# DC27-bottom-krux.net
KiCad netlist of a schematic drawn in EAGLE
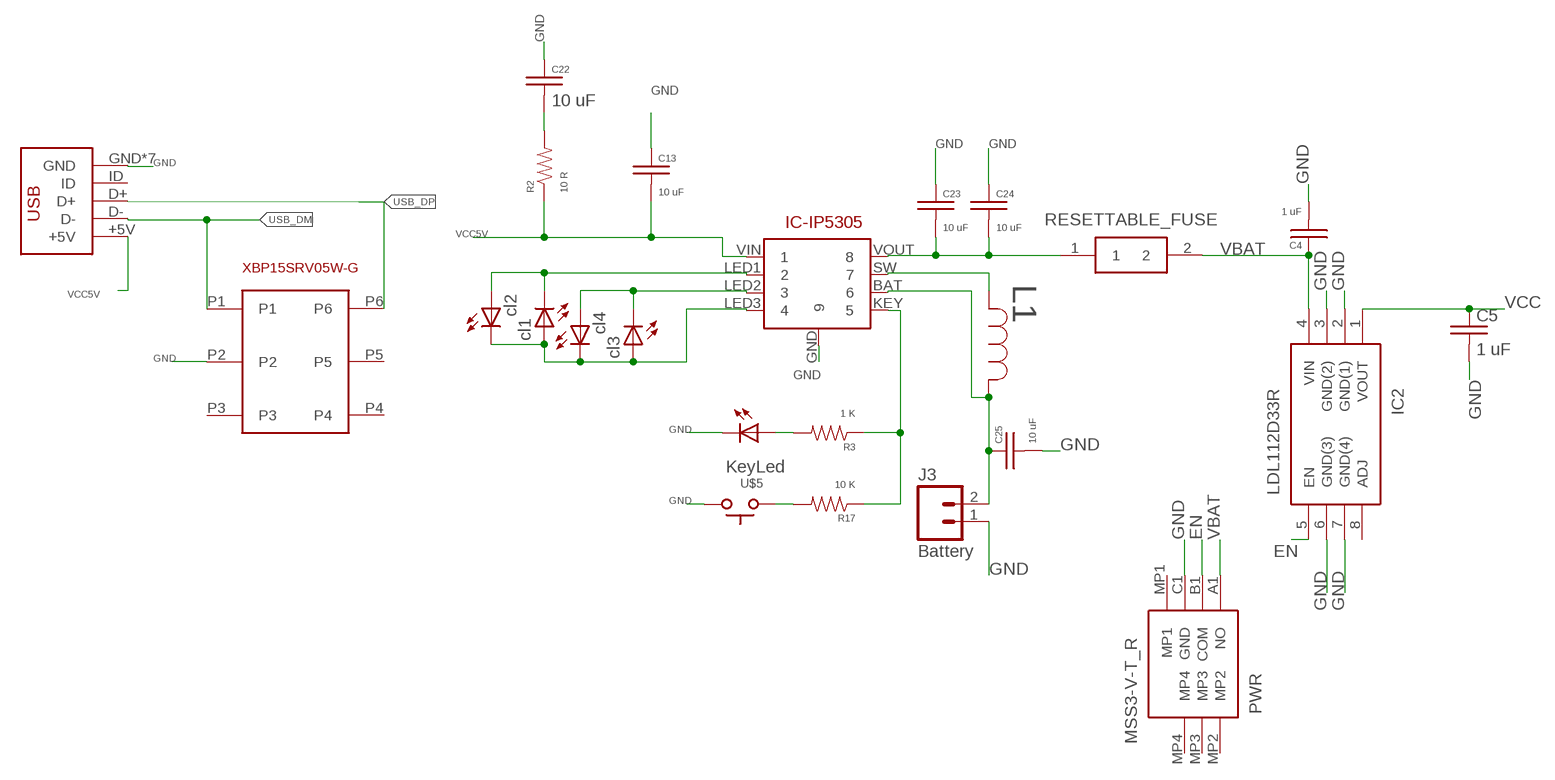
[diagram p0: schematic, sheet 1]
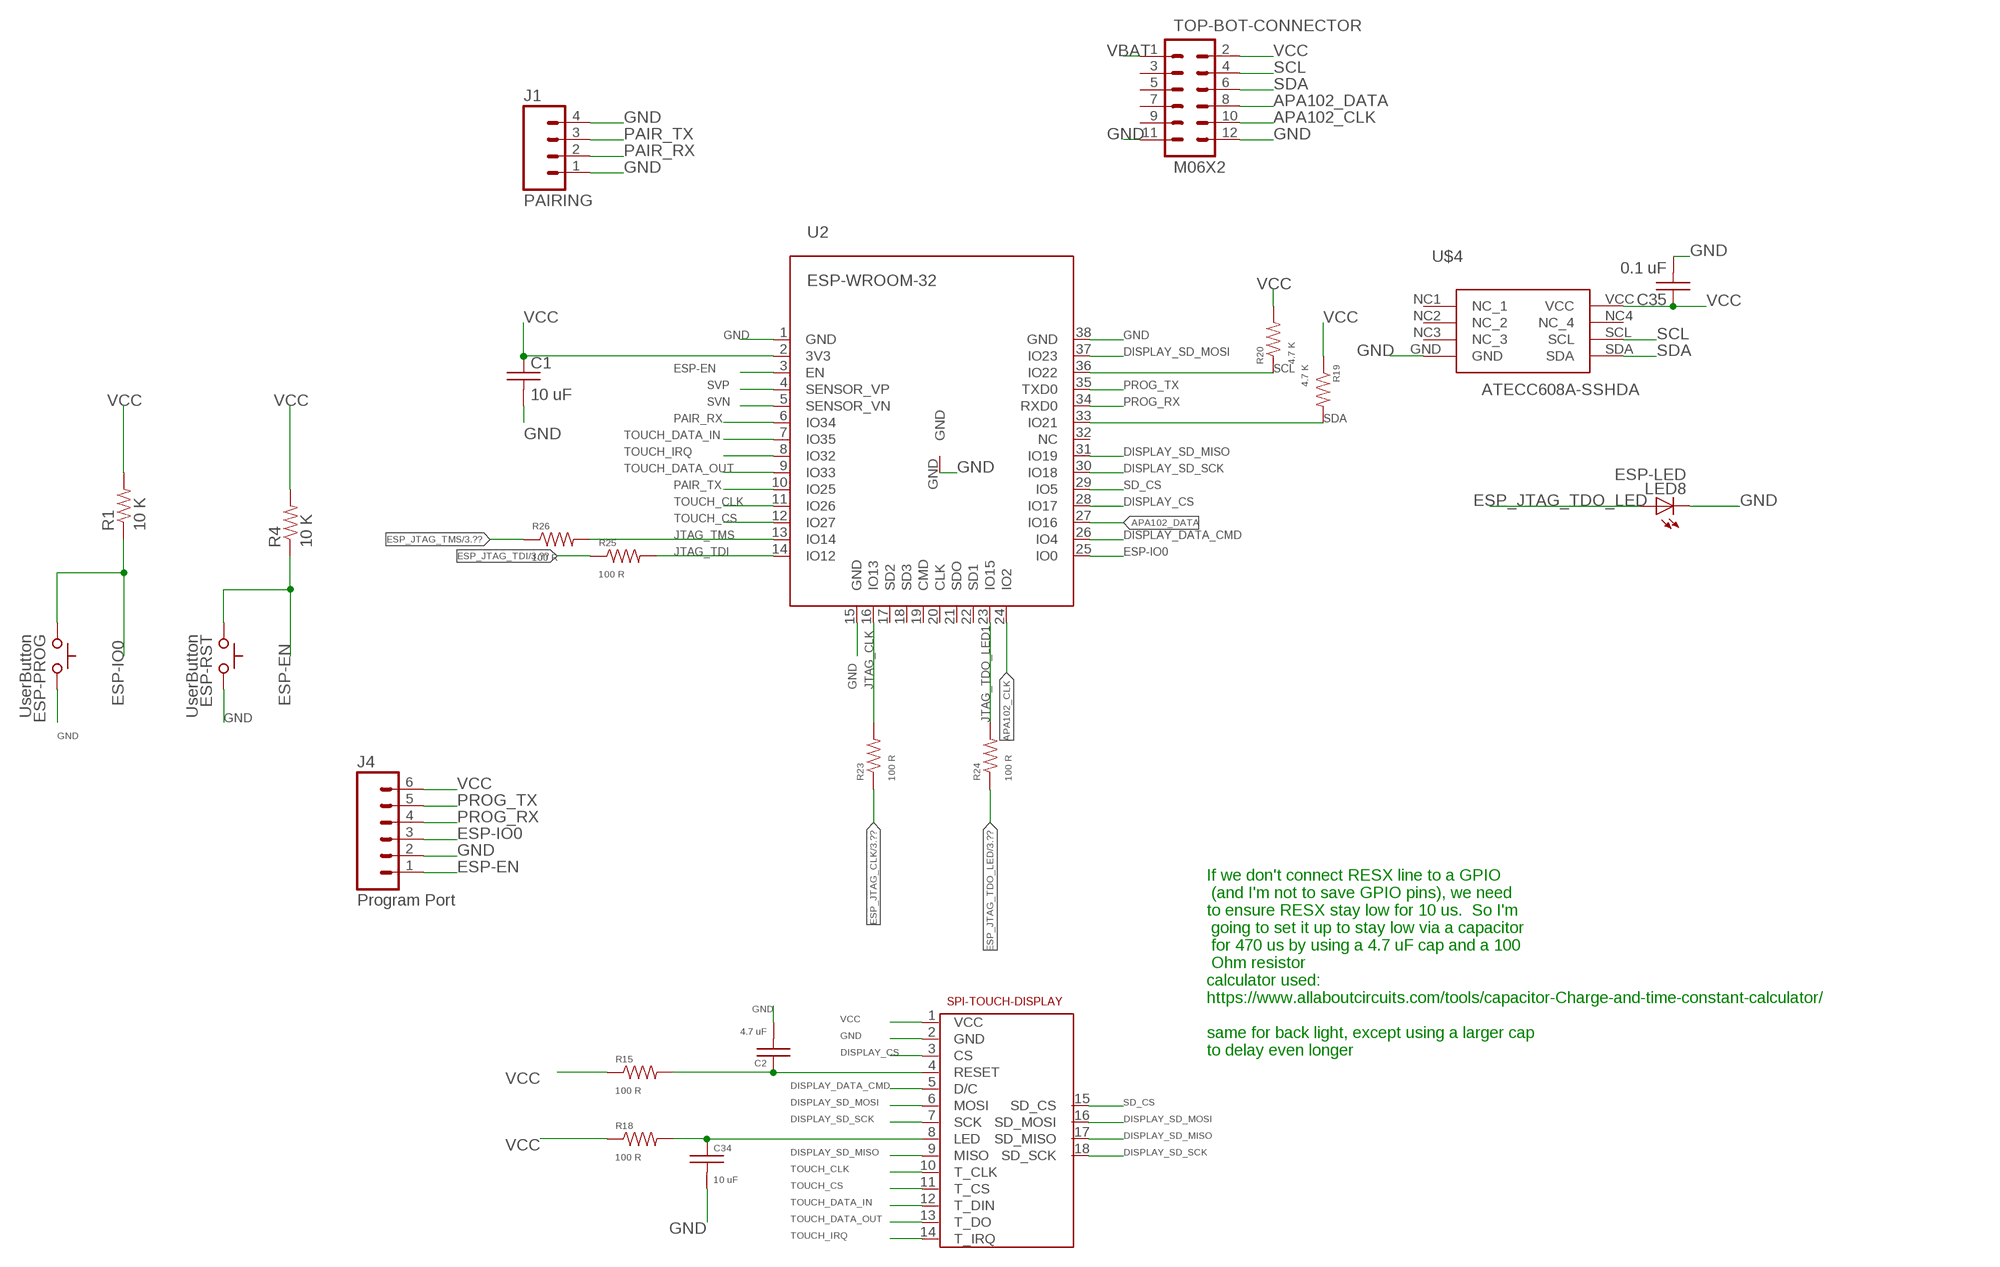
[diagram p1: schematic, sheet 2]
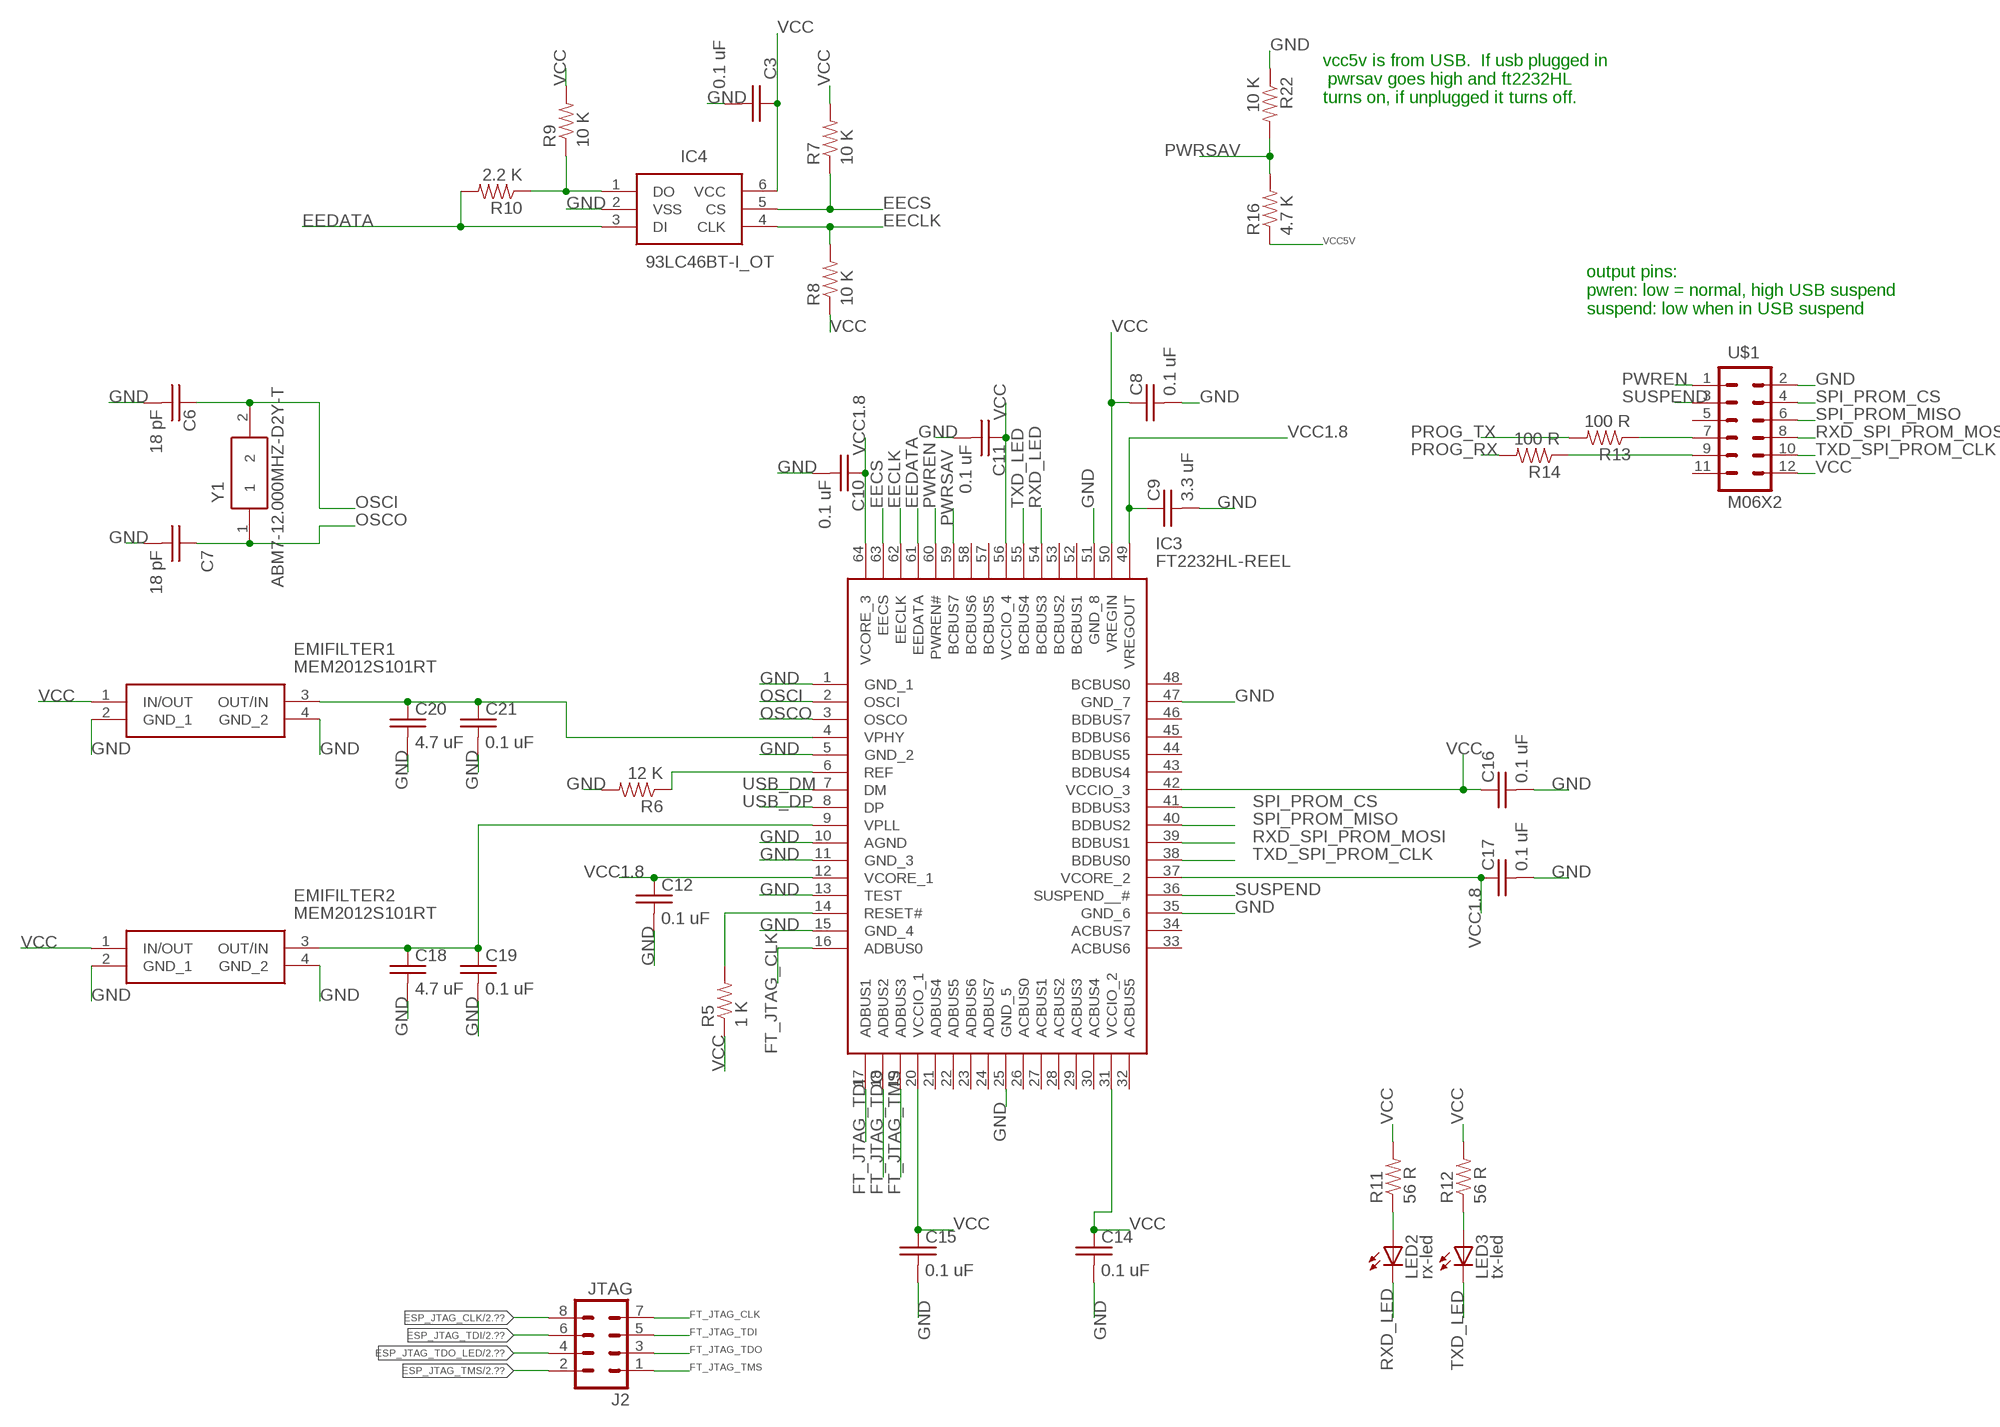
[diagram p2: schematic, sheet 3]
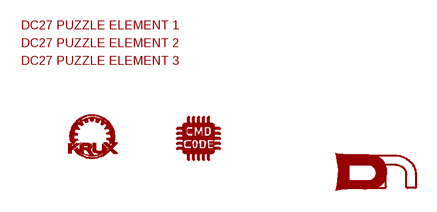
[diagram p3: schematic, sheet 4]

(export (version "E")
  (design (tool "Eeschema 10.0.6"))
  (components
    (comp (ref "C3")
      (value "0.1 uF")
      (footprint "eagle-import:C0805")
      (libsource (lib "eagle-import") (part "C-USC0805"))
    )
    (comp (ref "C6")
      (value "18 pF")
      (footprint "eagle-import:C0805")
      (libsource (lib "eagle-import") (part "C-USC0805"))
    )
    (comp (ref "C7")
      (value "18 pF")
      (footprint "eagle-import:C0805")
      (libsource (lib "eagle-import") (part "C-USC0805"))
    )
    (comp (ref "C8")
      (value "0.1 uF")
      (footprint "eagle-import:C0805")
      (libsource (lib "eagle-import") (part "C-USC0805"))
    )
    (comp (ref "C9")
      (value "3.3 uF")
      (footprint "eagle-import:C0805")
      (libsource (lib "eagle-import") (part "C-USC0805"))
    )
    (comp (ref "C10")
      (value "0.1 uF")
      (footprint "eagle-import:C0805")
      (libsource (lib "eagle-import") (part "C-USC0805"))
    )
    (comp (ref "C11")
      (value "0.1 uF")
      (footprint "eagle-import:C0805")
      (libsource (lib "eagle-import") (part "C-USC0805"))
    )
    (comp (ref "C12")
      (value "0.1 uF")
      (footprint "eagle-import:C0805")
      (libsource (lib "eagle-import") (part "C-USC0805"))
    )
    (comp (ref "C14")
      (value "0.1 uF")
      (footprint "eagle-import:C0805")
      (libsource (lib "eagle-import") (part "C-USC0805"))
    )
    (comp (ref "C15")
      (value "0.1 uF")
      (footprint "eagle-import:C0805")
      (libsource (lib "eagle-import") (part "C-USC0805"))
    )
    (comp (ref "C16")
      (value "0.1 uF")
      (footprint "eagle-import:C0805")
      (libsource (lib "eagle-import") (part "C-USC0805"))
    )
    (comp (ref "C17")
      (value "0.1 uF")
      (footprint "eagle-import:C0805")
      (libsource (lib "eagle-import") (part "C-USC0805"))
    )
    (comp (ref "C18")
      (value "4.7 uF")
      (footprint "eagle-import:C0805")
      (libsource (lib "eagle-import") (part "C-USC0805"))
    )
    (comp (ref "C19")
      (value "0.1 uF")
      (footprint "eagle-import:C0805")
      (libsource (lib "eagle-import") (part "C-USC0805"))
    )
    (comp (ref "C20")
      (value "4.7 uF")
      (footprint "eagle-import:C0805")
      (libsource (lib "eagle-import") (part "C-USC0805"))
    )
    (comp (ref "C21")
      (value "0.1 uF")
      (footprint "eagle-import:C0805")
      (libsource (lib "eagle-import") (part "C-USC0805"))
    )
    (comp (ref "EMIFILTER1")
      (value "MEM2012S101RT")
      (footprint "eagle-import:MEM2012S101RT")
      (libsource (lib "eagle-import") (part "MEM2012S101RT"))
    )
    (comp (ref "EMIFILTER2")
      (value "MEM2012S101RT")
      (footprint "eagle-import:MEM2012S101RT")
      (libsource (lib "eagle-import") (part "MEM2012S101RT"))
    )
    (comp (ref "IC3")
      (value "FT2232HL-REEL")
      (footprint "eagle-import:QFP50P1200X1200X160-64N")
      (fields (field (name "MOUSER_PART_NUMBER") "895-FT2232HL"))
      (libsource (lib "eagle-import") (part "FT2232HL-REEL"))
    )
    (comp (ref "IC4")
      (value "93LC46BT-I_OT")
      (footprint "eagle-import:SOT95P270X145-6N")
      (fields
        (field (name "MANUFACTURER_PART_NUMBER") "93LC46BT-I/OT")
        (field (name "MOUSER_PART_NUMBER") "579-93LC46BT-I/OT")
      )
      (libsource (lib "eagle-import") (part "93LC46BT-I_OT"))
    )
    (comp (ref "J2")
      (value "JTAG")
      (footprint "eagle-import:2X4")
      (libsource (lib "eagle-import") (part "M04X2"))
    )
    (comp (ref "LED2")
      (value "rx-led")
      (footprint "eagle-import:LED-1206")
      (libsource (lib "eagle-import") (part "LED1206"))
    )
    (comp (ref "LED3")
      (value "tx-led")
      (footprint "eagle-import:LED-1206")
      (libsource (lib "eagle-import") (part "LED1206"))
    )
    (comp (ref "R5")
      (value "1 K")
      (footprint "eagle-import:0805")
      (libsource (lib "eagle-import") (part "passives_RESISTOR0805-RES"))
    )
    (comp (ref "R6")
      (value "12 K")
      (footprint "eagle-import:0805")
      (libsource (lib "eagle-import") (part "passives_RESISTOR0805-RES"))
    )
    (comp (ref "R7")
      (value "10 K")
      (footprint "eagle-import:0805")
      (libsource (lib "eagle-import") (part "passives_RESISTOR0805-RES"))
    )
    (comp (ref "R8")
      (value "10 K")
      (footprint "eagle-import:0805")
      (libsource (lib "eagle-import") (part "passives_RESISTOR0805-RES"))
    )
    (comp (ref "R9")
      (value "10 K")
      (footprint "eagle-import:0805")
      (libsource (lib "eagle-import") (part "passives_RESISTOR0805-RES"))
    )
    (comp (ref "R10")
      (value "2.2 K")
      (footprint "eagle-import:0805")
      (libsource (lib "eagle-import") (part "passives_RESISTOR0805-RES"))
    )
    (comp (ref "R11")
      (value "56 R")
      (footprint "eagle-import:0805")
      (libsource (lib "eagle-import") (part "passives_RESISTOR0805-RES"))
    )
    (comp (ref "R12")
      (value "56 R")
      (footprint "eagle-import:0805")
      (libsource (lib "eagle-import") (part "passives_RESISTOR0805-RES"))
    )
    (comp (ref "R13")
      (value "100 R")
      (footprint "eagle-import:0805")
      (libsource (lib "eagle-import") (part "passives_RESISTOR0805-RES"))
    )
    (comp (ref "R14")
      (value "100 R")
      (footprint "eagle-import:0805")
      (libsource (lib "eagle-import") (part "passives_RESISTOR0805-RES"))
    )
    (comp (ref "R16")
      (value "4.7 K")
      (footprint "eagle-import:0805")
      (libsource (lib "eagle-import") (part "passives_RESISTOR0805-RES"))
    )
    (comp (ref "R22")
      (value "10 K")
      (footprint "eagle-import:0805")
      (libsource (lib "eagle-import") (part "passives_RESISTOR0805-RES"))
    )
    (comp (ref "U$1")
      (value "M06X2")
      (footprint "eagle-import:2X6")
      (libsource (lib "eagle-import") (part "M06X2"))
    )
    (comp (ref "Y1")
      (value "ABM7-12.000MHZ-D2Y-T")
      (footprint "eagle-import:ABM7")
      (fields
        (field (name "MOUSER_PART_NUMBER") "815-ABM7-12-D2Y-T")
        (field (name "RS_PART_NUMBER") "1710625P")
      )
      (libsource (lib "eagle-import") (part "ABM7-12.000MHZ-D2Y-T"))
    )
    (comp (ref "C1")
      (value "10 uF")
      (footprint "eagle-import:C0805")
      (libsource (lib "eagle-import") (part "C-USC0805"))
    )
    (comp (ref "C2")
      (value "4.7 uF")
      (footprint "eagle-import:C0805")
      (libsource (lib "eagle-import") (part "C-USC0805"))
    )
    (comp (ref "C34")
      (value "10 uF")
      (footprint "eagle-import:C0805")
      (libsource (lib "eagle-import") (part "C-USC0805"))
    )
    (comp (ref "C35")
      (value "0.1 uF")
      (footprint "eagle-import:C0805")
      (libsource (lib "eagle-import") (part "C-USC0805"))
    )
    (comp (ref "ESP-PROG")
      (value "UserButton")
      (footprint "eagle-import:TACTILE-2PIN-NARROW")
      (libsource (lib "eagle-import") (part "SWITCH_TACTILETACTILE-2PIN-NARROW"))
    )
    (comp (ref "ESP-RST")
      (value "UserButton")
      (footprint "eagle-import:TACTILE-2PIN-NARROW")
      (libsource (lib "eagle-import") (part "SWITCH_TACTILETACTILE-2PIN-NARROW"))
    )
    (comp (ref "J1")
      (value "PAIRING")
      (footprint "eagle-import:1X04")
      (libsource (lib "eagle-import") (part "M04PTH"))
    )
    (comp (ref "J4")
      (value "Program Port")
      (footprint "eagle-import:1X06-SMD-POGO")
      (libsource (lib "eagle-import") (part "M06POGO-PIN"))
    )
    (comp (ref "LED8")
      (value "ESP-LED")
      (footprint "eagle-import:LED-1206")
      (libsource (lib "eagle-import") (part "LED1206"))
    )
    (comp (ref "R1")
      (value "10 K")
      (footprint "eagle-import:0805")
      (libsource (lib "eagle-import") (part "RESISTOR0805-RES"))
    )
    (comp (ref "R4")
      (value "10 K")
      (footprint "eagle-import:0805")
      (libsource (lib "eagle-import") (part "RESISTOR0805-RES"))
    )
    (comp (ref "R15")
      (value "100 R")
      (footprint "eagle-import:0805")
      (libsource (lib "eagle-import") (part "RESISTOR0805-RES"))
    )
    (comp (ref "R18")
      (value "100 R")
      (footprint "eagle-import:0805")
      (libsource (lib "eagle-import") (part "RESISTOR0805-RES"))
    )
    (comp (ref "R19")
      (value "4.7 K")
      (footprint "eagle-import:0805")
      (libsource (lib "eagle-import") (part "RESISTOR0805-RES"))
    )
    (comp (ref "R20")
      (value "4.7 K")
      (footprint "eagle-import:0805")
      (libsource (lib "eagle-import") (part "RESISTOR0805-RES"))
    )
    (comp (ref "R23")
      (value "100 R")
      (footprint "eagle-import:0805")
      (libsource (lib "eagle-import") (part "RESISTOR0805-RES"))
    )
    (comp (ref "R24")
      (value "100 R")
      (footprint "eagle-import:0805")
      (libsource (lib "eagle-import") (part "RESISTOR0805-RES"))
    )
    (comp (ref "R25")
      (value "100 R")
      (footprint "eagle-import:0805")
      (libsource (lib "eagle-import") (part "RESISTOR0805-RES"))
    )
    (comp (ref "R26")
      (value "100 R")
      (footprint "eagle-import:0805")
      (libsource (lib "eagle-import") (part "RESISTOR0805-RES"))
    )
    (comp (ref "TOP-BOT-CONNECTOR")
      (value "M06X2")
      (footprint "eagle-import:2X6")
      (libsource (lib "eagle-import") (part "M06X2"))
    )
    (comp (ref "U$4")
      (value "ATECC608A-SSHDA")
      (footprint "eagle-import:8-SOIC")
      (libsource (lib "eagle-import") (part "ATECC608A-SSHDA"))
    )
    (comp (ref "U$10")
      (value "2.4-SPI-TFT-TOUCH-SSD-MODULE")
      (footprint "eagle-import:2.4-SPI-TFT-TOUCH-SSD-MODULE")
      (libsource (lib "eagle-import") (part "2.4-SPI-TFT-TOUCH-SSD-MODULE"))
    )
    (comp (ref "U2")
      (value "ESP-WROOM-32")
      (footprint "eagle-import:ESP-WROOM-32")
      (libsource (lib "eagle-import") (part "ESP-WROOM-32"))
    )
    (comp (ref "U$6")
      (value "DC27_PUZZLE_ELEMENT_1")
      (footprint "eagle-import:DC27_PUZZLE_ELEMENT_1")
      (libsource (lib "eagle-import") (part "DC27_PUZZLE_ELEMENT_1"))
    )
    (comp (ref "U$7")
      (value "DC27_PUZZLE_ELEMENT_3")
      (footprint "eagle-import:DC27_PUZZLE_ELEMENT_3")
      (libsource (lib "eagle-import") (part "DC27_PUZZLE_ELEMENT_3"))
    )
    (comp (ref "U$8")
      (value "CMD_C0DE_LOGO")
      (footprint "eagle-import:CMD_C0DE_LOGO")
      (libsource (lib "eagle-import") (part "CMD_C0DE_LOGO"))
    )
    (comp (ref "U$9")
      (value "DN_LOGO")
      (footprint "eagle-import:DN_LOGO_LONG_SILK")
      (libsource (lib "eagle-import") (part "DN_LOGO"))
    )
    (comp (ref "U$11")
      (value "DC27_PUZZLE_ELEMENT_2")
      (footprint "eagle-import:DC27_PUZZLE_ELEMENT_2")
      (libsource (lib "eagle-import") (part "DC27_PUZZLE_ELEMENT_2"))
    )
    (comp (ref "U$12")
      (value "KRUX_LOGO")
      (footprint "eagle-import:KRUX_LOGO")
      (libsource (lib "eagle-import") (part "KRUX_LOGO"))
    )
    (comp (ref "C4")
      (value "1 uF")
      (footprint "eagle-import:C0805")
      (libsource (lib "eagle-import") (part "C-USC0805"))
    )
    (comp (ref "C5")
      (value "1 uF")
      (footprint "eagle-import:C0805")
      (libsource (lib "eagle-import") (part "C-USC0805"))
    )
    (comp (ref "C13")
      (value "10 uF")
      (footprint "eagle-import:C0805")
      (libsource (lib "eagle-import") (part "C-USC0805"))
    )
    (comp (ref "C22")
      (value "10 uF")
      (footprint "eagle-import:C0805")
      (libsource (lib "eagle-import") (part "C-USC0805"))
    )
    (comp (ref "C23")
      (value "10 uF")
      (footprint "eagle-import:C0805")
      (libsource (lib "eagle-import") (part "C-USC0805"))
    )
    (comp (ref "C24")
      (value "10 uF")
      (footprint "eagle-import:C0805")
      (libsource (lib "eagle-import") (part "C-USC0805"))
    )
    (comp (ref "C25")
      (value "10 uF")
      (footprint "eagle-import:C0805")
      (libsource (lib "eagle-import") (part "C-USC0805"))
    )
    (comp (ref "IC-IP5305")
      (value "IP5305ESOP8")
      (footprint "eagle-import:SOIC127P600X165-8")
      (libsource (lib "eagle-import") (part "IP5305ESOP8"))
    )
    (comp (ref "IC2")
      (value "LDL112D33R")
      (footprint "eagle-import:SOIC127P600X175-8N")
      (libsource (lib "eagle-import") (part "LDL112D33R"))
    )
    (comp (ref "J3")
      (value "Battery")
      (footprint "eagle-import:JST-2-PTH")
      (libsource (lib "eagle-import") (part "M02JST-PTH-2"))
    )
    (comp (ref "L1")
      (value "2.2uH")
      (footprint "eagle-import:IND_TAIYO_NRS4018")
      (fields (field (name "MANUFACTURER_PART_NUMBER") "NRS4018T2R2MDGJ"))
      (libsource (lib "eagle-import") (part "NRS4018T2R2MDGJ"))
    )
    (comp (ref "LED1")
      (value "cl1")
      (footprint "eagle-import:LED-1206")
      (libsource (lib "eagle-import") (part "LED1206"))
    )
    (comp (ref "LED4")
      (value "cl2")
      (footprint "eagle-import:LED-1206")
      (libsource (lib "eagle-import") (part "LED1206"))
    )
    (comp (ref "LED5")
      (value "cl3")
      (footprint "eagle-import:LED-1206")
      (libsource (lib "eagle-import") (part "LED1206"))
    )
    (comp (ref "LED6")
      (value "cl4")
      (footprint "eagle-import:LED-1206")
      (libsource (lib "eagle-import") (part "LED1206"))
    )
    (comp (ref "LED7")
      (value "KeyLed")
      (footprint "eagle-import:LED-1206")
      (libsource (lib "eagle-import") (part "LED1206"))
    )
    (comp (ref "PWR")
      (value "MSS3-V-T_R")
      (footprint "eagle-import:MSS3VTR")
      (fields
        (field (name "MANUFACTURER_PART_NUMBER") "MSS3-V-T/R")
        (field (name "MOUSER_PART_NUMBER") "113-MSS3-V-T/R")
      )
      (libsource (lib "eagle-import") (part "MSS3-V-T_R"))
    )
    (comp (ref "R2")
      (value "10 R")
      (footprint "eagle-import:0805")
      (libsource (lib "eagle-import") (part "passives_RESISTOR0805-RES"))
    )
    (comp (ref "R3")
      (value "1 K")
      (footprint "eagle-import:0805")
      (libsource (lib "eagle-import") (part "passives_RESISTOR0805-RES"))
    )
    (comp (ref "R17")
      (value "10 K")
      (footprint "eagle-import:0805")
      (libsource (lib "eagle-import") (part "passives_RESISTOR0805-RES"))
    )
    (comp (ref "RESETTABLE_FUSE")
      (value "0ZCJ0050FF2G")
      (footprint "eagle-import:FUSC3216X55N")
      (libsource (lib "eagle-import") (part "0ZCJ0050FF2G"))
    )
    (comp (ref "U$2")
      (value "XBP15SRV05W-G")
      (footprint "eagle-import:SOT-26P-XBP15SRV05W-G")
      (fields (field (name "DIGI_KEY_PART_NUMBER") "893-1422-1-ND"))
      (libsource (lib "eagle-import") (part "XBP15SRV05W-G"))
    )
    (comp (ref "U$3")
      (value "DX4R005JJ2DX4R005JJ2")
      (footprint "eagle-import:DX4R005JJ2")
      (libsource (lib "eagle-import") (part "DX4R005JJ2DX4R005JJ2"))
    )
    (comp (ref "U$5")
      (value "SWITCH_TACTILETACTILE-2PIN-NARROW")
      (footprint "eagle-import:TACTILE-2PIN-NARROW")
      (libsource (lib "eagle-import") (part "switches_SWITCH_TACTILETACTILE-2PIN-NARROW"))
    )
  )
  (nets
    (net (code "1") (name "APA102_CLK") (class "Default")
      (node (ref "TOP-BOT-CONNECTOR") (pin "10") (pinfunction "10_10") (pintype "passive"))
      (node (ref "U2") (pin "24") (pinfunction "IO2_24") (pintype "bidirectional"))
    )
    (net (code "2") (name "APA102_DATA") (class "Default")
      (node (ref "TOP-BOT-CONNECTOR") (pin "8") (pinfunction "8_8") (pintype "passive"))
      (node (ref "U2") (pin "27") (pinfunction "IO16_27") (pintype "bidirectional"))
    )
    (net (code "3") (name "DISPLAY_CS") (class "Default")
      (node (ref "U$10") (pin "3") (pinfunction "CS_3") (pintype "bidirectional"))
      (node (ref "U2") (pin "28") (pinfunction "IO17_28") (pintype "bidirectional"))
    )
    (net (code "4") (name "DISPLAY_DATA_CMD") (class "Default")
      (node (ref "U$10") (pin "5") (pinfunction "D/C_5") (pintype "bidirectional"))
      (node (ref "U2") (pin "26") (pinfunction "IO4_26") (pintype "bidirectional"))
    )
    (net (code "5") (name "DISPLAY_SD_MISO") (class "Default")
      (node (ref "U$10") (pin "17") (pinfunction "SD_MISO_17") (pintype "bidirectional"))
      (node (ref "U$10") (pin "9") (pinfunction "MISO_9") (pintype "bidirectional"))
      (node (ref "U2") (pin "31") (pinfunction "IO19_31") (pintype "bidirectional"))
    )
    (net (code "6") (name "DISPLAY_SD_MOSI") (class "Default")
      (node (ref "U$10") (pin "16") (pinfunction "SD_MOSI_16") (pintype "bidirectional"))
      (node (ref "U$10") (pin "6") (pinfunction "MOSI_6") (pintype "bidirectional"))
      (node (ref "U2") (pin "37") (pinfunction "IO23_37") (pintype "bidirectional"))
    )
    (net (code "7") (name "DISPLAY_SD_SCK") (class "Default")
      (node (ref "U$10") (pin "18") (pinfunction "SD_SCK_18") (pintype "bidirectional"))
      (node (ref "U$10") (pin "7") (pinfunction "SCK_7") (pintype "bidirectional"))
      (node (ref "U2") (pin "30") (pinfunction "IO18_30") (pintype "bidirectional"))
    )
    (net (code "8") (name "EECLK") (class "Default")
      (node (ref "IC3") (pin "62") (pinfunction "EECLK_62") (pintype "bidirectional"))
      (node (ref "IC4") (pin "4") (pinfunction "CLK_4") (pintype "input"))
      (node (ref "R8") (pin "2") (pinfunction "2_2") (pintype "passive"))
    )
    (net (code "9") (name "EECS") (class "Default")
      (node (ref "IC3") (pin "63") (pinfunction "EECS_63") (pintype "bidirectional"))
      (node (ref "IC4") (pin "5") (pinfunction "CS_5") (pintype "input"))
      (node (ref "R7") (pin "1") (pinfunction "1_1") (pintype "passive"))
    )
    (net (code "10") (name "EEDATA") (class "Default")
      (node (ref "IC3") (pin "61") (pinfunction "EEDATA_61") (pintype "bidirectional"))
      (node (ref "IC4") (pin "3") (pinfunction "DI_3") (pintype "bidirectional"))
      (node (ref "R10") (pin "2") (pinfunction "2_2") (pintype "passive"))
    )
    (net (code "11") (name "EN") (class "Default")
      (node (ref "IC2") (pin "5") (pinfunction "EN_5") (pintype "bidirectional"))
      (node (ref "PWR") (pin "B1") (pinfunction "COM_B1") (pintype "bidirectional"))
    )
    (net (code "12") (name "ESP-EN") (class "Default")
      (node (ref "ESP-RST") (pin "P$2") (pinfunction "C_P$2") (pintype "passive"))
      (node (ref "J4") (pin "1") (pinfunction "1_1") (pintype "passive"))
      (node (ref "R4") (pin "1") (pinfunction "1_1") (pintype "passive"))
      (node (ref "U2") (pin "3") (pinfunction "EN_3") (pintype "bidirectional"))
    )
    (net (code "13") (name "ESP-IO0") (class "Default")
      (node (ref "ESP-PROG") (pin "P$2") (pinfunction "C_P$2") (pintype "passive"))
      (node (ref "J4") (pin "3") (pinfunction "3_3") (pintype "passive"))
      (node (ref "R1") (pin "1") (pinfunction "1_1") (pintype "passive"))
      (node (ref "U2") (pin "25") (pinfunction "IO0_25") (pintype "bidirectional"))
    )
    (net (code "14") (name "ESP_JTAG_CLK") (class "Default")
      (node (ref "J2") (pin "8") (pinfunction "8_8") (pintype "passive"))
      (node (ref "R23") (pin "1") (pinfunction "1_1") (pintype "passive"))
    )
    (net (code "15") (name "ESP_JTAG_TDI") (class "Default")
      (node (ref "J2") (pin "6") (pinfunction "6_6") (pintype "passive"))
      (node (ref "R25") (pin "1") (pinfunction "1_1") (pintype "passive"))
    )
    (net (code "16") (name "ESP_JTAG_TDO_LED") (class "Default")
      (node (ref "J2") (pin "4") (pinfunction "4_4") (pintype "passive"))
      (node (ref "LED8") (pin "A") (pinfunction "A_A") (pintype "input"))
      (node (ref "R24") (pin "1") (pinfunction "1_1") (pintype "passive"))
    )
    (net (code "17") (name "ESP_JTAG_TMS") (class "Default")
      (node (ref "J2") (pin "2") (pinfunction "2_2") (pintype "passive"))
      (node (ref "R26") (pin "1") (pinfunction "1_1") (pintype "passive"))
    )
    (net (code "18") (name "FT_JTAG_CLK") (class "Default")
      (node (ref "IC3") (pin "16") (pinfunction "ADBUS0_16") (pintype "bidirectional"))
      (node (ref "J2") (pin "7") (pinfunction "7_7") (pintype "passive"))
    )
    (net (code "19") (name "FT_JTAG_TDI") (class "Default")
      (node (ref "IC3") (pin "17") (pinfunction "ADBUS1_17") (pintype "bidirectional"))
      (node (ref "J2") (pin "5") (pinfunction "5_5") (pintype "passive"))
    )
    (net (code "20") (name "FT_JTAG_TDO") (class "Default")
      (node (ref "IC3") (pin "18") (pinfunction "ADBUS2_18") (pintype "bidirectional"))
      (node (ref "J2") (pin "3") (pinfunction "3_3") (pintype "passive"))
    )
    (net (code "21") (name "FT_JTAG_TMS") (class "Default")
      (node (ref "IC3") (pin "19") (pinfunction "ADBUS3_19") (pintype "bidirectional"))
      (node (ref "J2") (pin "1") (pinfunction "1_1") (pintype "passive"))
    )
    (net (code "22") (name "GND") (class "Default")
      (node (ref "C1") (pin "2") (pinfunction "2_2") (pintype "passive"))
      (node (ref "C10") (pin "2") (pinfunction "2_2") (pintype "passive"))
      (node (ref "C11") (pin "2") (pinfunction "2_2") (pintype "passive"))
      (node (ref "C12") (pin "2") (pinfunction "2_2") (pintype "passive"))
      (node (ref "C13") (pin "1") (pinfunction "1_1") (pintype "passive"))
      (node (ref "C14") (pin "2") (pinfunction "2_2") (pintype "passive"))
      (node (ref "C15") (pin "2") (pinfunction "2_2") (pintype "passive"))
      (node (ref "C16") (pin "2") (pinfunction "2_2") (pintype "passive"))
      (node (ref "C17") (pin "2") (pinfunction "2_2") (pintype "passive"))
      (node (ref "C18") (pin "2") (pinfunction "2_2") (pintype "passive"))
      (node (ref "C19") (pin "2") (pinfunction "2_2") (pintype "passive"))
      (node (ref "C2") (pin "2") (pinfunction "2_2") (pintype "passive"))
      (node (ref "C20") (pin "2") (pinfunction "2_2") (pintype "passive"))
      (node (ref "C21") (pin "2") (pinfunction "2_2") (pintype "passive"))
      (node (ref "C22") (pin "1") (pinfunction "1_1") (pintype "passive"))
      (node (ref "C23") (pin "1") (pinfunction "1_1") (pintype "passive"))
      (node (ref "C24") (pin "1") (pinfunction "1_1") (pintype "passive"))
      (node (ref "C25") (pin "2") (pinfunction "2_2") (pintype "passive"))
      (node (ref "C3") (pin "2") (pinfunction "2_2") (pintype "passive"))
      (node (ref "C34") (pin "2") (pinfunction "2_2") (pintype "passive"))
      (node (ref "C35") (pin "2") (pinfunction "2_2") (pintype "passive"))
      (node (ref "C4") (pin "2") (pinfunction "2_2") (pintype "passive"))
      (node (ref "C5") (pin "2") (pinfunction "2_2") (pintype "passive"))
      (node (ref "C6") (pin "2") (pinfunction "2_2") (pintype "passive"))
      (node (ref "C7") (pin "2") (pinfunction "2_2") (pintype "passive"))
      (node (ref "C8") (pin "2") (pinfunction "2_2") (pintype "passive"))
      (node (ref "C9") (pin "2") (pinfunction "2_2") (pintype "passive"))
      (node (ref "EMIFILTER1") (pin "2") (pinfunction "GND_1_2") (pintype "bidirectional"))
      (node (ref "EMIFILTER1") (pin "4") (pinfunction "GND_2_4") (pintype "bidirectional"))
      (node (ref "EMIFILTER2") (pin "2") (pinfunction "GND_1_2") (pintype "bidirectional"))
      (node (ref "EMIFILTER2") (pin "4") (pinfunction "GND_2_4") (pintype "bidirectional"))
      (node (ref "ESP-PROG") (pin "P$1") (pinfunction "A_P$1") (pintype "passive"))
      (node (ref "ESP-RST") (pin "P$1") (pinfunction "A_P$1") (pintype "passive"))
      (node (ref "IC-IP5305") (pin "GND") (pinfunction "9_GND") (pintype "bidirectional"))
      (node (ref "IC2") (pin "2") (pinfunction "GND(1)_2") (pintype "bidirectional"))
      (node (ref "IC2") (pin "3") (pinfunction "GND(2)_3") (pintype "bidirectional"))
      (node (ref "IC2") (pin "6") (pinfunction "GND(3)_6") (pintype "bidirectional"))
      (node (ref "IC2") (pin "7") (pinfunction "GND(4)_7") (pintype "bidirectional"))
      (node (ref "IC3") (pin "1") (pinfunction "GND_1_1") (pintype "bidirectional"))
      (node (ref "IC3") (pin "10") (pinfunction "AGND_10") (pintype "bidirectional"))
      (node (ref "IC3") (pin "11") (pinfunction "GND_3_11") (pintype "bidirectional"))
      (node (ref "IC3") (pin "13") (pinfunction "TEST_13") (pintype "bidirectional"))
      (node (ref "IC3") (pin "15") (pinfunction "GND_4_15") (pintype "bidirectional"))
      (node (ref "IC3") (pin "25") (pinfunction "GND_5_25") (pintype "bidirectional"))
      (node (ref "IC3") (pin "35") (pinfunction "GND_6_35") (pintype "bidirectional"))
      (node (ref "IC3") (pin "47") (pinfunction "GND_7_47") (pintype "bidirectional"))
      (node (ref "IC3") (pin "5") (pinfunction "GND_2_5") (pintype "bidirectional"))
      (node (ref "IC3") (pin "51") (pinfunction "GND_8_51") (pintype "bidirectional"))
      (node (ref "IC4") (pin "2") (pinfunction "VSS_2") (pintype "power_in"))
      (node (ref "J1") (pin "1") (pinfunction "1_1") (pintype "passive"))
      (node (ref "J1") (pin "4") (pinfunction "4_4") (pintype "passive"))
      (node (ref "J3") (pin "1") (pinfunction "1_1") (pintype "passive"))
      (node (ref "J4") (pin "2") (pinfunction "2_2") (pintype "passive"))
      (node (ref "LED7") (pin "C") (pinfunction "C_C") (pintype "output"))
      (node (ref "LED8") (pin "C") (pinfunction "C_C") (pintype "output"))
      (node (ref "PWR") (pin "C1") (pinfunction "GND_C1") (pintype "bidirectional"))
      (node (ref "R22") (pin "1") (pinfunction "1_1") (pintype "passive"))
      (node (ref "R6") (pin "2") (pinfunction "2_2") (pintype "passive"))
      (node (ref "TOP-BOT-CONNECTOR") (pin "11") (pinfunction "11_11") (pintype "passive"))
      (node (ref "TOP-BOT-CONNECTOR") (pin "12") (pinfunction "12_12") (pintype "passive"))
      (node (ref "U$1") (pin "2") (pinfunction "2_2") (pintype "passive"))
      (node (ref "U$10") (pin "2") (pinfunction "GND_2") (pintype "power_in"))
      (node (ref "U$2") (pin "P2") (pinfunction "P2_P2") (pintype "bidirectional"))
      (node (ref "U$3") (pin "GND") (pinfunction "GND_GND") (pintype "bidirectional"))
      (node (ref "U$3") (pin "P$10") (pinfunction "GND_P$10") (pintype "bidirectional"))
      (node (ref "U$3") (pin "P$11") (pinfunction "GND_P$11") (pintype "bidirectional"))
      (node (ref "U$3") (pin "P$6") (pinfunction "GND_P$6") (pintype "bidirectional"))
      (node (ref "U$3") (pin "P$7") (pinfunction "GND_P$7") (pintype "bidirectional"))
      (node (ref "U$3") (pin "P$8") (pinfunction "GND_P$8") (pintype "bidirectional"))
      (node (ref "U$3") (pin "P$9") (pinfunction "GND_P$9") (pintype "bidirectional"))
      (node (ref "U$4") (pin "GND") (pinfunction "GND_GND") (pintype "power_in"))
      (node (ref "U$5") (pin "P$1") (pinfunction "A_P$1") (pintype "passive"))
      (node (ref "U2") (pin "1") (pinfunction "GND_1") (pintype "bidirectional"))
      (node (ref "U2") (pin "15") (pinfunction "GND_15") (pintype "bidirectional"))
      (node (ref "U2") (pin "38") (pinfunction "GND_38") (pintype "bidirectional"))
      (node (ref "U2") (pin "GND") (pinfunction "GND_GND") (pintype "bidirectional"))
    )
    (net (code "23") (name "JTAG_CLK") (class "Default")
      (node (ref "R23") (pin "2") (pinfunction "2_2") (pintype "passive"))
      (node (ref "U2") (pin "16") (pinfunction "IO13_16") (pintype "bidirectional"))
    )
    (net (code "24") (name "JTAG_TDI") (class "Default")
      (node (ref "R25") (pin "2") (pinfunction "2_2") (pintype "passive"))
      (node (ref "U2") (pin "14") (pinfunction "IO12_14") (pintype "bidirectional"))
    )
    (net (code "25") (name "JTAG_TDO_LED1") (class "Default")
      (node (ref "R24") (pin "2") (pinfunction "2_2") (pintype "passive"))
      (node (ref "U2") (pin "23") (pinfunction "IO15_23") (pintype "bidirectional"))
    )
    (net (code "26") (name "JTAG_TMS") (class "Default")
      (node (ref "R26") (pin "2") (pinfunction "2_2") (pintype "passive"))
      (node (ref "U2") (pin "13") (pinfunction "IO14_13") (pintype "bidirectional"))
    )
    (net (code "27") (name "Net-(C22-Pad2)") (class "Default")
      (node (ref "C22") (pin "2") (pinfunction "2_2") (pintype "passive"))
      (node (ref "R2") (pin "2") (pinfunction "2_2") (pintype "passive"))
    )
    (net (code "28") (name "Net-(EMIFILTER1-OUT{slash}IN)") (class "Default")
      (node (ref "C20") (pin "1") (pinfunction "1_1") (pintype "passive"))
      (node (ref "C21") (pin "1") (pinfunction "1_1") (pintype "passive"))
      (node (ref "EMIFILTER1") (pin "3") (pinfunction "OUT/IN_3") (pintype "bidirectional"))
      (node (ref "IC3") (pin "4") (pinfunction "VPHY_4") (pintype "bidirectional"))
    )
    (net (code "29") (name "Net-(EMIFILTER2-OUT{slash}IN)") (class "Default")
      (node (ref "C18") (pin "1") (pinfunction "1_1") (pintype "passive"))
      (node (ref "C19") (pin "1") (pinfunction "1_1") (pintype "passive"))
      (node (ref "EMIFILTER2") (pin "3") (pinfunction "OUT/IN_3") (pintype "bidirectional"))
      (node (ref "IC3") (pin "9") (pinfunction "VPLL_9") (pintype "bidirectional"))
    )
    (net (code "30") (name "Net-(IC-IP5305-2)") (class "Default")
      (node (ref "IC-IP5305") (pin "LED1") (pinfunction "2_LED1") (pintype "output"))
      (node (ref "LED1") (pin "A") (pinfunction "A_A") (pintype "input"))
      (node (ref "LED4") (pin "C") (pinfunction "C_C") (pintype "output"))
    )
    (net (code "31") (name "Net-(IC-IP5305-3)") (class "Default")
      (node (ref "IC-IP5305") (pin "LED2") (pinfunction "3_LED2") (pintype "output"))
      (node (ref "LED5") (pin "A") (pinfunction "A_A") (pintype "input"))
      (node (ref "LED6") (pin "C") (pinfunction "C_C") (pintype "output"))
    )
    (net (code "32") (name "Net-(IC-IP5305-4)") (class "Default")
      (node (ref "IC-IP5305") (pin "LED3") (pinfunction "4_LED3") (pintype "output"))
      (node (ref "LED1") (pin "C") (pinfunction "C_C") (pintype "output"))
      (node (ref "LED4") (pin "A") (pinfunction "A_A") (pintype "input"))
      (node (ref "LED5") (pin "C") (pinfunction "C_C") (pintype "output"))
      (node (ref "LED6") (pin "A") (pinfunction "A_A") (pintype "input"))
    )
    (net (code "33") (name "Net-(IC-IP5305-5)") (class "Default")
      (node (ref "IC-IP5305") (pin "KEY") (pinfunction "5_KEY") (pintype "bidirectional"))
      (node (ref "R17") (pin "1") (pinfunction "1_1") (pintype "passive"))
      (node (ref "R3") (pin "1") (pinfunction "1_1") (pintype "passive"))
    )
    (net (code "34") (name "Net-(IC-IP5305-6)") (class "Default")
      (node (ref "C25") (pin "1") (pinfunction "1_1") (pintype "passive"))
      (node (ref "IC-IP5305") (pin "BAT") (pinfunction "6_BAT") (pintype "bidirectional"))
      (node (ref "J3") (pin "2") (pinfunction "2_2") (pintype "passive"))
      (node (ref "L1") (pin "1") (pinfunction "1_1") (pintype "passive"))
    )
    (net (code "35") (name "Net-(IC-IP5305-7)") (class "Default")
      (node (ref "IC-IP5305") (pin "SW") (pinfunction "7_SW") (pintype "bidirectional"))
      (node (ref "L1") (pin "2") (pinfunction "2_2") (pintype "passive"))
    )
    (net (code "36") (name "Net-(IC-IP5305-8)") (class "Default")
      (node (ref "C23") (pin "2") (pinfunction "2_2") (pintype "passive"))
      (node (ref "C24") (pin "2") (pinfunction "2_2") (pintype "passive"))
      (node (ref "IC-IP5305") (pin "VOUT") (pinfunction "8_VOUT") (pintype "bidirectional"))
      (node (ref "RESETTABLE_FUSE") (pin "1") (pinfunction "1_1") (pintype "passive"))
    )
    (net (code "37") (name "Net-(IC3-REF)") (class "Default")
      (node (ref "IC3") (pin "6") (pinfunction "REF_6") (pintype "bidirectional"))
      (node (ref "R6") (pin "1") (pinfunction "1_1") (pintype "passive"))
    )
    (net (code "38") (name "Net-(IC3-RESET#)") (class "Default")
      (node (ref "IC3") (pin "14") (pinfunction "RESET#_14") (pintype "bidirectional"))
      (node (ref "R5") (pin "2") (pinfunction "2_2") (pintype "passive"))
    )
    (net (code "39") (name "Net-(IC4-DO)") (class "Default")
      (node (ref "IC4") (pin "1") (pinfunction "DO_1") (pintype "bidirectional"))
      (node (ref "R10") (pin "1") (pinfunction "1_1") (pintype "passive"))
      (node (ref "R9") (pin "1") (pinfunction "1_1") (pintype "passive"))
    )
    (net (code "40") (name "Net-(LED2-PadA)") (class "Default")
      (node (ref "LED2") (pin "A") (pinfunction "A_A") (pintype "input"))
      (node (ref "R11") (pin "1") (pinfunction "1_1") (pintype "passive"))
    )
    (net (code "41") (name "Net-(LED3-PadA)") (class "Default")
      (node (ref "LED3") (pin "A") (pinfunction "A_A") (pintype "input"))
      (node (ref "R12") (pin "1") (pinfunction "1_1") (pintype "passive"))
    )
    (net (code "42") (name "Net-(LED7-PadA)") (class "Default")
      (node (ref "LED7") (pin "A") (pinfunction "A_A") (pintype "input"))
      (node (ref "R3") (pin "2") (pinfunction "2_2") (pintype "passive"))
    )
    (net (code "43") (name "Net-(R13-Pad1)") (class "Default")
      (node (ref "R13") (pin "1") (pinfunction "1_1") (pintype "passive"))
      (node (ref "U$1") (pin "7") (pinfunction "7_7") (pintype "passive"))
    )
    (net (code "44") (name "Net-(R14-Pad1)") (class "Default")
      (node (ref "R14") (pin "1") (pinfunction "1_1") (pintype "passive"))
      (node (ref "U$1") (pin "9") (pinfunction "9_9") (pintype "passive"))
    )
    (net (code "45") (name "Net-(U$5-C)") (class "Default")
      (node (ref "R17") (pin "2") (pinfunction "2_2") (pintype "passive"))
      (node (ref "U$5") (pin "P$2") (pinfunction "C_P$2") (pintype "passive"))
    )
    (net (code "46") (name "Net-(U$10-LED)") (class "Default")
      (node (ref "C34") (pin "1") (pinfunction "1_1") (pintype "passive"))
      (node (ref "R18") (pin "2") (pinfunction "2_2") (pintype "passive"))
      (node (ref "U$10") (pin "8") (pinfunction "LED_8") (pintype "bidirectional"))
    )
    (net (code "47") (name "Net-(U$10-RESET)") (class "Default")
      (node (ref "C2") (pin "1") (pinfunction "1_1") (pintype "passive"))
      (node (ref "R15") (pin "2") (pinfunction "2_2") (pintype "passive"))
      (node (ref "U$10") (pin "4") (pinfunction "RESET_4") (pintype "bidirectional"))
    )
    (net (code "48") (name "OSCI") (class "Default")
      (node (ref "C6") (pin "1") (pinfunction "1_1") (pintype "passive"))
      (node (ref "IC3") (pin "2") (pinfunction "OSCI_2") (pintype "bidirectional"))
      (node (ref "Y1") (pin "2") (pinfunction "2_2") (pintype "bidirectional"))
    )
    (net (code "49") (name "OSCO") (class "Default")
      (node (ref "C7") (pin "1") (pinfunction "1_1") (pintype "passive"))
      (node (ref "IC3") (pin "3") (pinfunction "OSCO_3") (pintype "bidirectional"))
      (node (ref "Y1") (pin "1") (pinfunction "1_1") (pintype "bidirectional"))
    )
    (net (code "50") (name "PAIR_RX") (class "Default")
      (node (ref "J1") (pin "2") (pinfunction "2_2") (pintype "passive"))
      (node (ref "U2") (pin "6") (pinfunction "IO34_6") (pintype "bidirectional"))
    )
    (net (code "51") (name "PAIR_TX") (class "Default")
      (node (ref "J1") (pin "3") (pinfunction "3_3") (pintype "passive"))
      (node (ref "U2") (pin "10") (pinfunction "IO25_10") (pintype "bidirectional"))
    )
    (net (code "52") (name "PROG_RX") (class "Default")
      (node (ref "J4") (pin "4") (pinfunction "4_4") (pintype "passive"))
      (node (ref "R14") (pin "2") (pinfunction "2_2") (pintype "passive"))
      (node (ref "U2") (pin "34") (pinfunction "RXD0_34") (pintype "bidirectional"))
    )
    (net (code "53") (name "PROG_TX") (class "Default")
      (node (ref "J4") (pin "5") (pinfunction "5_5") (pintype "passive"))
      (node (ref "R13") (pin "2") (pinfunction "2_2") (pintype "passive"))
      (node (ref "U2") (pin "35") (pinfunction "TXD0_35") (pintype "bidirectional"))
    )
    (net (code "54") (name "PWREN") (class "Default")
      (node (ref "IC3") (pin "60") (pinfunction "PWREN#_60") (pintype "bidirectional"))
      (node (ref "U$1") (pin "1") (pinfunction "1_1") (pintype "passive"))
    )
    (net (code "55") (name "PWRSAV") (class "Default")
      (node (ref "IC3") (pin "59") (pinfunction "BCBUS7_59") (pintype "bidirectional"))
      (node (ref "R16") (pin "2") (pinfunction "2_2") (pintype "passive"))
      (node (ref "R22") (pin "2") (pinfunction "2_2") (pintype "passive"))
    )
    (net (code "56") (name "RXD_LED") (class "Default")
      (node (ref "IC3") (pin "54") (pinfunction "BCBUS3_54") (pintype "bidirectional"))
      (node (ref "LED2") (pin "C") (pinfunction "C_C") (pintype "output"))
    )
    (net (code "57") (name "RXD_SPI_PROM_MOSI") (class "Default")
      (node (ref "IC3") (pin "39") (pinfunction "BDBUS1_39") (pintype "bidirectional"))
      (node (ref "U$1") (pin "8") (pinfunction "8_8") (pintype "passive"))
    )
    (net (code "58") (name "SCL") (class "Default")
      (node (ref "R20") (pin "1") (pinfunction "1_1") (pintype "passive"))
      (node (ref "TOP-BOT-CONNECTOR") (pin "4") (pinfunction "4_4") (pintype "passive"))
      (node (ref "U$4") (pin "SCL") (pinfunction "SCL_SCL") (pintype "bidirectional"))
      (node (ref "U2") (pin "36") (pinfunction "IO22_36") (pintype "bidirectional"))
    )
    (net (code "59") (name "SDA") (class "Default")
      (node (ref "R19") (pin "2") (pinfunction "2_2") (pintype "passive"))
      (node (ref "TOP-BOT-CONNECTOR") (pin "6") (pinfunction "6_6") (pintype "passive"))
      (node (ref "U$4") (pin "SDA") (pinfunction "SDA_SDA") (pintype "bidirectional"))
      (node (ref "U2") (pin "33") (pinfunction "IO21_33") (pintype "bidirectional"))
    )
    (net (code "60") (name "SD_CS") (class "Default")
      (node (ref "U$10") (pin "15") (pinfunction "SD_CS_15") (pintype "bidirectional"))
      (node (ref "U2") (pin "29") (pinfunction "IO5_29") (pintype "bidirectional"))
    )
    (net (code "61") (name "SPI_PROM_CS") (class "Default")
      (node (ref "IC3") (pin "41") (pinfunction "BDBUS3_41") (pintype "bidirectional"))
      (node (ref "U$1") (pin "4") (pinfunction "4_4") (pintype "passive"))
    )
    (net (code "62") (name "SPI_PROM_MISO") (class "Default")
      (node (ref "IC3") (pin "40") (pinfunction "BDBUS2_40") (pintype "bidirectional"))
      (node (ref "U$1") (pin "6") (pinfunction "6_6") (pintype "passive"))
    )
    (net (code "63") (name "SUSPEND") (class "Default")
      (node (ref "IC3") (pin "36") (pinfunction "SUSPEND__#_36") (pintype "bidirectional"))
      (node (ref "U$1") (pin "3") (pinfunction "3_3") (pintype "passive"))
    )
    (net (code "64") (name "SVN") (class "Default")
      (node (ref "U2") (pin "5") (pinfunction "SENSOR_VN_5") (pintype "bidirectional"))
    )
    (net (code "65") (name "SVP") (class "Default")
      (node (ref "U2") (pin "4") (pinfunction "SENSOR_VP_4") (pintype "bidirectional"))
    )
    (net (code "66") (name "TOUCH_CLK") (class "Default")
      (node (ref "U$10") (pin "10") (pinfunction "T_CLK_10") (pintype "bidirectional"))
      (node (ref "U2") (pin "11") (pinfunction "IO26_11") (pintype "bidirectional"))
    )
    (net (code "67") (name "TOUCH_CS") (class "Default")
      (node (ref "U$10") (pin "11") (pinfunction "T_CS_11") (pintype "bidirectional"))
      (node (ref "U2") (pin "12") (pinfunction "IO27_12") (pintype "bidirectional"))
    )
    (net (code "68") (name "TOUCH_DATA_IN") (class "Default")
      (node (ref "U$10") (pin "12") (pinfunction "T_DIN_12") (pintype "bidirectional"))
      (node (ref "U2") (pin "7") (pinfunction "IO35_7") (pintype "bidirectional"))
    )
    (net (code "69") (name "TOUCH_DATA_OUT") (class "Default")
      (node (ref "U$10") (pin "13") (pinfunction "T_DO_13") (pintype "bidirectional"))
      (node (ref "U2") (pin "9") (pinfunction "IO33_9") (pintype "bidirectional"))
    )
    (net (code "70") (name "TOUCH_IRQ") (class "Default")
      (node (ref "U$10") (pin "14") (pinfunction "T_IRQ_14") (pintype "bidirectional"))
      (node (ref "U2") (pin "8") (pinfunction "IO32_8") (pintype "bidirectional"))
    )
    (net (code "71") (name "TXD_LED") (class "Default")
      (node (ref "IC3") (pin "55") (pinfunction "BCBUS4_55") (pintype "bidirectional"))
      (node (ref "LED3") (pin "C") (pinfunction "C_C") (pintype "output"))
    )
    (net (code "72") (name "TXD_SPI_PROM_CLK") (class "Default")
      (node (ref "IC3") (pin "38") (pinfunction "BDBUS0_38") (pintype "bidirectional"))
      (node (ref "U$1") (pin "10") (pinfunction "10_10") (pintype "passive"))
    )
    (net (code "73") (name "USB_DM") (class "Default")
      (node (ref "IC3") (pin "7") (pinfunction "DM_7") (pintype "bidirectional"))
      (node (ref "U$2") (pin "P1") (pinfunction "P1_P1") (pintype "bidirectional"))
      (node (ref "U$3") (pin "D-") (pinfunction "D-_D-") (pintype "bidirectional"))
    )
    (net (code "74") (name "USB_DP") (class "Default")
      (node (ref "IC3") (pin "8") (pinfunction "DP_8") (pintype "bidirectional"))
      (node (ref "U$2") (pin "P6") (pinfunction "P6_P6") (pintype "bidirectional"))
      (node (ref "U$3") (pin "D+") (pinfunction "D+_D+") (pintype "bidirectional"))
    )
    (net (code "75") (name "VBAT") (class "Default")
      (node (ref "C4") (pin "1") (pinfunction "1_1") (pintype "passive"))
      (node (ref "IC2") (pin "4") (pinfunction "VIN_4") (pintype "bidirectional"))
      (node (ref "PWR") (pin "A1") (pinfunction "NO_A1") (pintype "bidirectional"))
      (node (ref "RESETTABLE_FUSE") (pin "2") (pinfunction "2_2") (pintype "passive"))
      (node (ref "TOP-BOT-CONNECTOR") (pin "1") (pinfunction "1_1") (pintype "passive"))
    )
    (net (code "76") (name "VCC") (class "Default")
      (node (ref "C1") (pin "1") (pinfunction "1_1") (pintype "passive"))
      (node (ref "C11") (pin "1") (pinfunction "1_1") (pintype "passive"))
      (node (ref "C14") (pin "1") (pinfunction "1_1") (pintype "passive"))
      (node (ref "C15") (pin "1") (pinfunction "1_1") (pintype "passive"))
      (node (ref "C16") (pin "1") (pinfunction "1_1") (pintype "passive"))
      (node (ref "C3") (pin "1") (pinfunction "1_1") (pintype "passive"))
      (node (ref "C35") (pin "1") (pinfunction "1_1") (pintype "passive"))
      (node (ref "C5") (pin "1") (pinfunction "1_1") (pintype "passive"))
      (node (ref "C8") (pin "1") (pinfunction "1_1") (pintype "passive"))
      (node (ref "EMIFILTER1") (pin "1") (pinfunction "IN/OUT_1") (pintype "bidirectional"))
      (node (ref "EMIFILTER2") (pin "1") (pinfunction "IN/OUT_1") (pintype "bidirectional"))
      (node (ref "IC2") (pin "1") (pinfunction "VOUT_1") (pintype "bidirectional"))
      (node (ref "IC3") (pin "20") (pinfunction "VCCIO_1_20") (pintype "bidirectional"))
      (node (ref "IC3") (pin "31") (pinfunction "VCCIO_2_31") (pintype "bidirectional"))
      (node (ref "IC3") (pin "42") (pinfunction "VCCIO_3_42") (pintype "bidirectional"))
      (node (ref "IC3") (pin "50") (pinfunction "VREGIN_50") (pintype "bidirectional"))
      (node (ref "IC3") (pin "56") (pinfunction "VCCIO_4_56") (pintype "bidirectional"))
      (node (ref "IC4") (pin "6") (pinfunction "VCC_6") (pintype "power_in"))
      (node (ref "J4") (pin "6") (pinfunction "6_6") (pintype "passive"))
      (node (ref "R1") (pin "2") (pinfunction "2_2") (pintype "passive"))
      (node (ref "R11") (pin "2") (pinfunction "2_2") (pintype "passive"))
      (node (ref "R12") (pin "2") (pinfunction "2_2") (pintype "passive"))
      (node (ref "R15") (pin "1") (pinfunction "1_1") (pintype "passive"))
      (node (ref "R18") (pin "1") (pinfunction "1_1") (pintype "passive"))
      (node (ref "R19") (pin "1") (pinfunction "1_1") (pintype "passive"))
      (node (ref "R20") (pin "2") (pinfunction "2_2") (pintype "passive"))
      (node (ref "R4") (pin "2") (pinfunction "2_2") (pintype "passive"))
      (node (ref "R5") (pin "1") (pinfunction "1_1") (pintype "passive"))
      (node (ref "R7") (pin "2") (pinfunction "2_2") (pintype "passive"))
      (node (ref "R8") (pin "1") (pinfunction "1_1") (pintype "passive"))
      (node (ref "R9") (pin "2") (pinfunction "2_2") (pintype "passive"))
      (node (ref "TOP-BOT-CONNECTOR") (pin "2") (pinfunction "2_2") (pintype "passive"))
      (node (ref "U$1") (pin "12") (pinfunction "12_12") (pintype "passive"))
      (node (ref "U$10") (pin "1") (pinfunction "VCC_1") (pintype "power_in"))
      (node (ref "U$4") (pin "VCC") (pinfunction "VCC_VCC") (pintype "power_in"))
      (node (ref "U2") (pin "2") (pinfunction "3V3_2") (pintype "bidirectional"))
    )
    (net (code "77") (name "VCC1.8") (class "Default")
      (node (ref "C10") (pin "1") (pinfunction "1_1") (pintype "passive"))
      (node (ref "C12") (pin "1") (pinfunction "1_1") (pintype "passive"))
      (node (ref "C17") (pin "1") (pinfunction "1_1") (pintype "passive"))
      (node (ref "C9") (pin "1") (pinfunction "1_1") (pintype "passive"))
      (node (ref "IC3") (pin "12") (pinfunction "VCORE_1_12") (pintype "bidirectional"))
      (node (ref "IC3") (pin "37") (pinfunction "VCORE_2_37") (pintype "bidirectional"))
      (node (ref "IC3") (pin "49") (pinfunction "VREGOUT_49") (pintype "bidirectional"))
      (node (ref "IC3") (pin "64") (pinfunction "VCORE_3_64") (pintype "bidirectional"))
    )
    (net (code "78") (name "VCC5V") (class "Default")
      (node (ref "C13") (pin "2") (pinfunction "2_2") (pintype "passive"))
      (node (ref "IC-IP5305") (pin "VIN") (pinfunction "1_VIN") (pintype "power_in"))
      (node (ref "R16") (pin "1") (pinfunction "1_1") (pintype "passive"))
      (node (ref "R2") (pin "1") (pinfunction "1_1") (pintype "passive"))
      (node (ref "U$3") (pin "+5V") (pinfunction "+5V_+5V") (pintype "bidirectional"))
    )
    (net (code "79") (name "unconnected-(IC2-ADJ-Pad8)") (class "Default")
      (node (ref "IC2") (pin "8") (pinfunction "ADJ_8") (pintype "bidirectional"))
    )
    (net (code "80") (name "unconnected-(IC3-ACBUS0-Pad26)") (class "Default")
      (node (ref "IC3") (pin "26") (pinfunction "ACBUS0_26") (pintype "bidirectional"))
    )
    (net (code "81") (name "unconnected-(IC3-ACBUS1-Pad27)") (class "Default")
      (node (ref "IC3") (pin "27") (pinfunction "ACBUS1_27") (pintype "bidirectional"))
    )
    (net (code "82") (name "unconnected-(IC3-ACBUS2-Pad28)") (class "Default")
      (node (ref "IC3") (pin "28") (pinfunction "ACBUS2_28") (pintype "bidirectional"))
    )
    (net (code "83") (name "unconnected-(IC3-ACBUS3-Pad29)") (class "Default")
      (node (ref "IC3") (pin "29") (pinfunction "ACBUS3_29") (pintype "bidirectional"))
    )
    (net (code "84") (name "unconnected-(IC3-ACBUS4-Pad30)") (class "Default")
      (node (ref "IC3") (pin "30") (pinfunction "ACBUS4_30") (pintype "bidirectional"))
    )
    (net (code "85") (name "unconnected-(IC3-ACBUS5-Pad32)") (class "Default")
      (node (ref "IC3") (pin "32") (pinfunction "ACBUS5_32") (pintype "bidirectional"))
    )
    (net (code "86") (name "unconnected-(IC3-ACBUS6-Pad33)") (class "Default")
      (node (ref "IC3") (pin "33") (pinfunction "ACBUS6_33") (pintype "bidirectional"))
    )
    (net (code "87") (name "unconnected-(IC3-ACBUS7-Pad34)") (class "Default")
      (node (ref "IC3") (pin "34") (pinfunction "ACBUS7_34") (pintype "bidirectional"))
    )
    (net (code "88") (name "unconnected-(IC3-ADBUS4-Pad21)") (class "Default")
      (node (ref "IC3") (pin "21") (pinfunction "ADBUS4_21") (pintype "bidirectional"))
    )
    (net (code "89") (name "unconnected-(IC3-ADBUS5-Pad22)") (class "Default")
      (node (ref "IC3") (pin "22") (pinfunction "ADBUS5_22") (pintype "bidirectional"))
    )
    (net (code "90") (name "unconnected-(IC3-ADBUS6-Pad23)") (class "Default")
      (node (ref "IC3") (pin "23") (pinfunction "ADBUS6_23") (pintype "bidirectional"))
    )
    (net (code "91") (name "unconnected-(IC3-ADBUS7-Pad24)") (class "Default")
      (node (ref "IC3") (pin "24") (pinfunction "ADBUS7_24") (pintype "bidirectional"))
    )
    (net (code "92") (name "unconnected-(IC3-BCBUS0-Pad48)") (class "Default")
      (node (ref "IC3") (pin "48") (pinfunction "BCBUS0_48") (pintype "bidirectional"))
    )
    (net (code "93") (name "unconnected-(IC3-BCBUS1-Pad52)") (class "Default")
      (node (ref "IC3") (pin "52") (pinfunction "BCBUS1_52") (pintype "bidirectional"))
    )
    (net (code "94") (name "unconnected-(IC3-BCBUS2-Pad53)") (class "Default")
      (node (ref "IC3") (pin "53") (pinfunction "BCBUS2_53") (pintype "bidirectional"))
    )
    (net (code "95") (name "unconnected-(IC3-BCBUS5-Pad57)") (class "Default")
      (node (ref "IC3") (pin "57") (pinfunction "BCBUS5_57") (pintype "bidirectional"))
    )
    (net (code "96") (name "unconnected-(IC3-BCBUS6-Pad58)") (class "Default")
      (node (ref "IC3") (pin "58") (pinfunction "BCBUS6_58") (pintype "bidirectional"))
    )
    (net (code "97") (name "unconnected-(IC3-BDBUS4-Pad43)") (class "Default")
      (node (ref "IC3") (pin "43") (pinfunction "BDBUS4_43") (pintype "bidirectional"))
    )
    (net (code "98") (name "unconnected-(IC3-BDBUS5-Pad44)") (class "Default")
      (node (ref "IC3") (pin "44") (pinfunction "BDBUS5_44") (pintype "bidirectional"))
    )
    (net (code "99") (name "unconnected-(IC3-BDBUS6-Pad45)") (class "Default")
      (node (ref "IC3") (pin "45") (pinfunction "BDBUS6_45") (pintype "bidirectional"))
    )
    (net (code "100") (name "unconnected-(IC3-BDBUS7-Pad46)") (class "Default")
      (node (ref "IC3") (pin "46") (pinfunction "BDBUS7_46") (pintype "bidirectional"))
    )
    (net (code "101") (name "unconnected-(PWR-PadMP1)") (class "Default")
      (node (ref "PWR") (pin "MP1") (pinfunction "MP1_MP1") (pintype "bidirectional"))
    )
    (net (code "102") (name "unconnected-(PWR-PadMP2)") (class "Default")
      (node (ref "PWR") (pin "MP2") (pinfunction "MP2_MP2") (pintype "bidirectional"))
    )
    (net (code "103") (name "unconnected-(PWR-PadMP3)") (class "Default")
      (node (ref "PWR") (pin "MP3") (pinfunction "MP3_MP3") (pintype "bidirectional"))
    )
    (net (code "104") (name "unconnected-(PWR-PadMP4)") (class "Default")
      (node (ref "PWR") (pin "MP4") (pinfunction "MP4_MP4") (pintype "bidirectional"))
    )
    (net (code "105") (name "unconnected-(TOP-BOT-CONNECTOR-Pad3)") (class "Default")
      (node (ref "TOP-BOT-CONNECTOR") (pin "3") (pinfunction "3_3") (pintype "passive"))
    )
    (net (code "106") (name "unconnected-(TOP-BOT-CONNECTOR-Pad5)") (class "Default")
      (node (ref "TOP-BOT-CONNECTOR") (pin "5") (pinfunction "5_5") (pintype "passive"))
    )
    (net (code "107") (name "unconnected-(TOP-BOT-CONNECTOR-Pad7)") (class "Default")
      (node (ref "TOP-BOT-CONNECTOR") (pin "7") (pinfunction "7_7") (pintype "passive"))
    )
    (net (code "108") (name "unconnected-(TOP-BOT-CONNECTOR-Pad9)") (class "Default")
      (node (ref "TOP-BOT-CONNECTOR") (pin "9") (pinfunction "9_9") (pintype "passive"))
    )
    (net (code "109") (name "unconnected-(U$1-Pad5)") (class "Default")
      (node (ref "U$1") (pin "5") (pinfunction "5_5") (pintype "passive"))
    )
    (net (code "110") (name "unconnected-(U$1-Pad11)") (class "Default")
      (node (ref "U$1") (pin "11") (pinfunction "11_11") (pintype "passive"))
    )
    (net (code "111") (name "unconnected-(U$2-PadP3)") (class "Default")
      (node (ref "U$2") (pin "P3") (pinfunction "P3_P3") (pintype "bidirectional"))
    )
    (net (code "112") (name "unconnected-(U$2-PadP4)") (class "Default")
      (node (ref "U$2") (pin "P4") (pinfunction "P4_P4") (pintype "bidirectional"))
    )
    (net (code "113") (name "unconnected-(U$2-PadP5)") (class "Default")
      (node (ref "U$2") (pin "P5") (pinfunction "P5_P5") (pintype "bidirectional"))
    )
    (net (code "114") (name "unconnected-(U$3-PadID)") (class "Default")
      (node (ref "U$3") (pin "ID") (pinfunction "ID_ID") (pintype "bidirectional"))
    )
    (net (code "115") (name "unconnected-(U$4-NC_1-PadNC1)") (class "Default")
      (node (ref "U$4") (pin "NC1") (pinfunction "NC_1_NC1") (pintype "no_connect"))
    )
    (net (code "116") (name "unconnected-(U$4-NC_2-PadNC2)") (class "Default")
      (node (ref "U$4") (pin "NC2") (pinfunction "NC_2_NC2") (pintype "no_connect"))
    )
    (net (code "117") (name "unconnected-(U$4-NC_3-PadNC3)") (class "Default")
      (node (ref "U$4") (pin "NC3") (pinfunction "NC_3_NC3") (pintype "no_connect"))
    )
    (net (code "118") (name "unconnected-(U$4-NC_4-PadNC4)") (class "Default")
      (node (ref "U$4") (pin "NC4") (pinfunction "NC_4_NC4") (pintype "no_connect"))
    )
    (net (code "119") (name "unconnected-(U2-CLK-Pad20)") (class "Default")
      (node (ref "U2") (pin "20") (pinfunction "CLK_20") (pintype "bidirectional"))
    )
    (net (code "120") (name "unconnected-(U2-CMD-Pad19)") (class "Default")
      (node (ref "U2") (pin "19") (pinfunction "CMD_19") (pintype "bidirectional"))
    )
    (net (code "121") (name "unconnected-(U2-NC-Pad32)") (class "Default")
      (node (ref "U2") (pin "32") (pinfunction "NC_32") (pintype "bidirectional"))
    )
    (net (code "122") (name "unconnected-(U2-SD1-Pad22)") (class "Default")
      (node (ref "U2") (pin "22") (pinfunction "SD1_22") (pintype "bidirectional"))
    )
    (net (code "123") (name "unconnected-(U2-SD2-Pad17)") (class "Default")
      (node (ref "U2") (pin "17") (pinfunction "SD2_17") (pintype "bidirectional"))
    )
    (net (code "124") (name "unconnected-(U2-SD3-Pad18)") (class "Default")
      (node (ref "U2") (pin "18") (pinfunction "SD3_18") (pintype "bidirectional"))
    )
    (net (code "125") (name "unconnected-(U2-SDO-Pad21)") (class "Default")
      (node (ref "U2") (pin "21") (pinfunction "SDO_21") (pintype "bidirectional"))
    )
  )
)
